# Ampli_FI2.net
KiCad netlist of a schematic drawn in Altium Designer
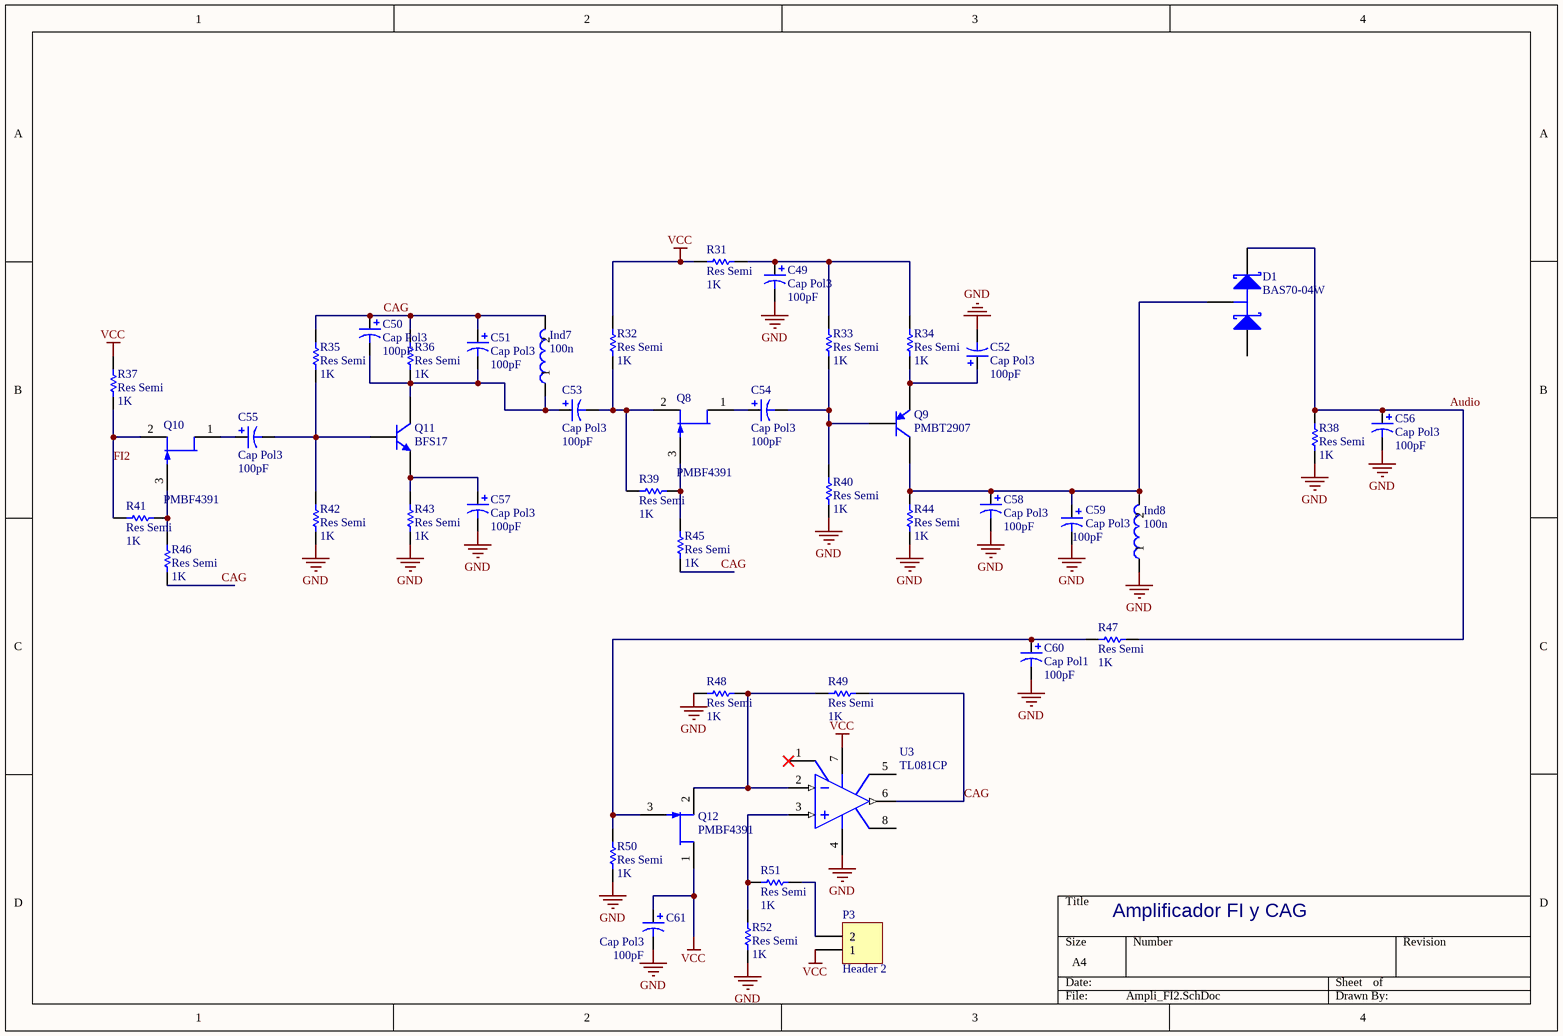
[diagram p0: Ampli_FI2.SchDoc]

(export (version "E")
  (design (tool "Eeschema 10.0.6"))
  (components
    (comp (ref "C49")
      (value "Cap Pol3")
      (footprint "C0805")
      (description "Polarized Capacitor (Surface Mount)")
      (fields (field (name "ALTIUM_VALUE") "100pF") (field (name "PUBLISHER") "Altium Limited"))
      (libsource (lib "Miscellaneous Devices") (part "Cap Pol3"))
    )
    (comp (ref "C50")
      (value "Cap Pol3")
      (footprint "C0805")
      (description "Polarized Capacitor (Surface Mount)")
      (fields (field (name "ALTIUM_VALUE") "100pF") (field (name "PUBLISHER") "Altium Limited"))
      (libsource (lib "Miscellaneous Devices") (part "Cap Pol3"))
    )
    (comp (ref "C51")
      (value "Cap Pol3")
      (footprint "C0805")
      (description "Polarized Capacitor (Surface Mount)")
      (fields (field (name "ALTIUM_VALUE") "100pF") (field (name "PUBLISHER") "Altium Limited"))
      (libsource (lib "Miscellaneous Devices") (part "Cap Pol3"))
    )
    (comp (ref "C52")
      (value "Cap Pol3")
      (footprint "C0805")
      (description "Polarized Capacitor (Surface Mount)")
      (fields (field (name "ALTIUM_VALUE") "100pF") (field (name "PUBLISHER") "Altium Limited"))
      (libsource (lib "Miscellaneous Devices") (part "Cap Pol3"))
    )
    (comp (ref "C53")
      (value "Cap Pol3")
      (footprint "C0805")
      (description "Polarized Capacitor (Surface Mount)")
      (fields (field (name "ALTIUM_VALUE") "100pF") (field (name "PUBLISHER") "Altium Limited"))
      (libsource (lib "Miscellaneous Devices") (part "Cap Pol3"))
    )
    (comp (ref "C54")
      (value "Cap Pol3")
      (footprint "C0805")
      (description "Polarized Capacitor (Surface Mount)")
      (fields (field (name "ALTIUM_VALUE") "100pF") (field (name "PUBLISHER") "Altium Limited"))
      (libsource (lib "Miscellaneous Devices") (part "Cap Pol3"))
    )
    (comp (ref "C55")
      (value "Cap Pol3")
      (footprint "C0805")
      (description "Polarized Capacitor (Surface Mount)")
      (fields (field (name "ALTIUM_VALUE") "100pF") (field (name "PUBLISHER") "Altium Limited"))
      (libsource (lib "Miscellaneous Devices") (part "Cap Pol3"))
    )
    (comp (ref "C56")
      (value "Cap Pol3")
      (footprint "C0805")
      (description "Polarized Capacitor (Surface Mount)")
      (fields (field (name "ALTIUM_VALUE") "100pF") (field (name "PUBLISHER") "Altium Limited"))
      (libsource (lib "Miscellaneous Devices") (part "Cap Pol3"))
    )
    (comp (ref "C57")
      (value "Cap Pol3")
      (footprint "C0805")
      (description "Polarized Capacitor (Surface Mount)")
      (fields (field (name "ALTIUM_VALUE") "100pF") (field (name "PUBLISHER") "Altium Limited"))
      (libsource (lib "Miscellaneous Devices") (part "Cap Pol3"))
    )
    (comp (ref "C58")
      (value "Cap Pol3")
      (footprint "C0805")
      (description "Polarized Capacitor (Surface Mount)")
      (fields (field (name "ALTIUM_VALUE") "100pF") (field (name "PUBLISHER") "Altium Limited"))
      (libsource (lib "Miscellaneous Devices") (part "Cap Pol3"))
    )
    (comp (ref "C59")
      (value "Cap Pol3")
      (footprint "C0805")
      (description "Polarized Capacitor (Surface Mount)")
      (fields (field (name "ALTIUM_VALUE") "100pF") (field (name "PUBLISHER") "Altium Limited"))
      (libsource (lib "Miscellaneous Devices") (part "Cap Pol3"))
    )
    (comp (ref "C60")
      (value "Cap Pol1")
      (footprint "B")
      (description "Polarized Capacitor (Radial)")
      (fields (field (name "ALTIUM_VALUE") "100pF") (field (name "PUBLISHER") "Altium Limited"))
      (libsource (lib "Miscellaneous Devices") (part "Cap Pol1"))
    )
    (comp (ref "C61")
      (value "Cap Pol3")
      (footprint "C0805")
      (description "Polarized Capacitor (Surface Mount)")
      (fields (field (name "ALTIUM_VALUE") "100pF") (field (name "PUBLISHER") "Altium Limited"))
      (libsource (lib "Miscellaneous Devices") (part "Cap Pol3"))
    )
    (comp (ref "D1")
      (value "BAS70-04W")
      (footprint "SOT323_N")
      (description "Schottky Barrier Double Diode")
      (fields (field (name "PUBLISHER") "Altium Limited"))
      (libsource (lib "Philips Discrete Diode - Schottky") (part "BAS70-04W"))
    )
    (comp (ref "Ind7")
      (value "Ind2")
      (footprint "AXIAL-0.3")
      (fields (field (name "VALOR") "100n"))
      (libsource (lib "epf") (part "Ind2"))
    )
    (comp (ref "Ind8")
      (value "Ind2")
      (footprint "AXIAL-0.3")
      (fields (field (name "VALOR") "100n"))
      (libsource (lib "epf") (part "Ind2"))
    )
    (comp (ref "P3")
      (value "Header 2")
      (footprint "HDR1X2")
      (description "Header, 2-Pin")
      (fields (field (name "PUBLISHER") "Altium Limited"))
      (libsource (lib "Miscellaneous Connectors") (part "Header 2"))
    )
    (comp (ref "Q8")
      (value "PMBF4391")
      (footprint "SOT-23")
      (description "N-channel Silicon Junction Field-effect Transistor")
      (fields (field (name "PUBLISHER") "Altium Limited"))
      (libsource (lib "Philips Discrete JFET") (part "PMBF4391"))
    )
    (comp (ref "Q9")
      (value "PMBT2907")
      (footprint "SOT-23")
      (description "PNP Switching Transistor")
      (fields (field (name "PUBLISHER") "Altium Limited"))
      (libsource (lib "Philips Discrete BJT - Low Power") (part "PMBT2907"))
    )
    (comp (ref "Q10")
      (value "PMBF4391")
      (footprint "SOT-23")
      (description "N-channel Silicon Junction Field-effect Transistor")
      (fields (field (name "PUBLISHER") "Altium Limited"))
      (libsource (lib "Philips Discrete JFET") (part "PMBF4391"))
    )
    (comp (ref "Q11")
      (value "BFS17")
      (footprint "SOT-23")
      (description "NPN 1 GHz Wideband Transistor")
      (fields (field (name "PUBLISHER") "Altium Limited"))
      (libsource (lib "Philips Discrete BJT - RF Transistor") (part "BFS17"))
    )
    (comp (ref "Q12")
      (value "PMBF4391")
      (footprint "SOT-23")
      (description "N-channel Silicon Junction Field-effect Transistor")
      (fields (field (name "PUBLISHER") "Altium Limited"))
      (libsource (lib "Philips Discrete JFET") (part "PMBF4391"))
    )
    (comp (ref "R31")
      (value "Res Semi")
      (footprint "2012[0805]")
      (description "Semiconductor Resistor")
      (fields (field (name "ALTIUM_VALUE") "1K") (field (name "PUBLISHER") "Altium Limited"))
      (libsource (lib "Miscellaneous Devices") (part "Res Semi"))
    )
    (comp (ref "R32")
      (value "Res Semi")
      (footprint "2012[0805]")
      (description "Semiconductor Resistor")
      (fields (field (name "ALTIUM_VALUE") "1K") (field (name "PUBLISHER") "Altium Limited"))
      (libsource (lib "Miscellaneous Devices") (part "Res Semi"))
    )
    (comp (ref "R33")
      (value "Res Semi")
      (footprint "2012[0805]")
      (description "Semiconductor Resistor")
      (fields (field (name "ALTIUM_VALUE") "1K") (field (name "PUBLISHER") "Altium Limited"))
      (libsource (lib "Miscellaneous Devices") (part "Res Semi"))
    )
    (comp (ref "R34")
      (value "Res Semi")
      (footprint "2012[0805]")
      (description "Semiconductor Resistor")
      (fields (field (name "ALTIUM_VALUE") "1K") (field (name "PUBLISHER") "Altium Limited"))
      (libsource (lib "Miscellaneous Devices") (part "Res Semi"))
    )
    (comp (ref "R35")
      (value "Res Semi")
      (footprint "2012[0805]")
      (description "Semiconductor Resistor")
      (fields (field (name "ALTIUM_VALUE") "1K") (field (name "PUBLISHER") "Altium Limited"))
      (libsource (lib "Miscellaneous Devices") (part "Res Semi"))
    )
    (comp (ref "R36")
      (value "Res Semi")
      (footprint "2012[0805]")
      (description "Semiconductor Resistor")
      (fields (field (name "ALTIUM_VALUE") "1K") (field (name "PUBLISHER") "Altium Limited"))
      (libsource (lib "Miscellaneous Devices") (part "Res Semi"))
    )
    (comp (ref "R37")
      (value "Res Semi")
      (footprint "2012[0805]")
      (description "Semiconductor Resistor")
      (fields (field (name "ALTIUM_VALUE") "1K") (field (name "PUBLISHER") "Altium Limited"))
      (libsource (lib "Miscellaneous Devices") (part "Res Semi"))
    )
    (comp (ref "R38")
      (value "Res Semi")
      (footprint "2012[0805]")
      (description "Semiconductor Resistor")
      (fields (field (name "ALTIUM_VALUE") "1K") (field (name "PUBLISHER") "Altium Limited"))
      (libsource (lib "Miscellaneous Devices") (part "Res Semi"))
    )
    (comp (ref "R39")
      (value "Res Semi")
      (footprint "2012[0805]")
      (description "Semiconductor Resistor")
      (fields (field (name "ALTIUM_VALUE") "1K") (field (name "PUBLISHER") "Altium Limited"))
      (libsource (lib "Miscellaneous Devices") (part "Res Semi"))
    )
    (comp (ref "R40")
      (value "Res Semi")
      (footprint "2012[0805]")
      (description "Semiconductor Resistor")
      (fields (field (name "ALTIUM_VALUE") "1K") (field (name "PUBLISHER") "Altium Limited"))
      (libsource (lib "Miscellaneous Devices") (part "Res Semi"))
    )
    (comp (ref "R41")
      (value "Res Semi")
      (footprint "2012[0805]")
      (description "Semiconductor Resistor")
      (fields (field (name "ALTIUM_VALUE") "1K") (field (name "PUBLISHER") "Altium Limited"))
      (libsource (lib "Miscellaneous Devices") (part "Res Semi"))
    )
    (comp (ref "R42")
      (value "Res Semi")
      (footprint "2012[0805]")
      (description "Semiconductor Resistor")
      (fields (field (name "ALTIUM_VALUE") "1K") (field (name "PUBLISHER") "Altium Limited"))
      (libsource (lib "Miscellaneous Devices") (part "Res Semi"))
    )
    (comp (ref "R43")
      (value "Res Semi")
      (footprint "2012[0805]")
      (description "Semiconductor Resistor")
      (fields (field (name "ALTIUM_VALUE") "1K") (field (name "PUBLISHER") "Altium Limited"))
      (libsource (lib "Miscellaneous Devices") (part "Res Semi"))
    )
    (comp (ref "R44")
      (value "Res Semi")
      (footprint "2012[0805]")
      (description "Semiconductor Resistor")
      (fields (field (name "ALTIUM_VALUE") "1K") (field (name "PUBLISHER") "Altium Limited"))
      (libsource (lib "Miscellaneous Devices") (part "Res Semi"))
    )
    (comp (ref "R45")
      (value "Res Semi")
      (footprint "2012[0805]")
      (description "Semiconductor Resistor")
      (fields (field (name "ALTIUM_VALUE") "1K") (field (name "PUBLISHER") "Altium Limited"))
      (libsource (lib "Miscellaneous Devices") (part "Res Semi"))
    )
    (comp (ref "R46")
      (value "Res Semi")
      (footprint "2012[0805]")
      (description "Semiconductor Resistor")
      (fields (field (name "ALTIUM_VALUE") "1K") (field (name "PUBLISHER") "Altium Limited"))
      (libsource (lib "Miscellaneous Devices") (part "Res Semi"))
    )
    (comp (ref "R47")
      (value "Res Semi")
      (footprint "2012[0805]")
      (description "Semiconductor Resistor")
      (fields (field (name "ALTIUM_VALUE") "1K") (field (name "PUBLISHER") "Altium Limited"))
      (libsource (lib "Miscellaneous Devices") (part "Res Semi"))
    )
    (comp (ref "R48")
      (value "Res Semi")
      (footprint "2012[0805]")
      (description "Semiconductor Resistor")
      (fields (field (name "ALTIUM_VALUE") "1K") (field (name "PUBLISHER") "Altium Limited"))
      (libsource (lib "Miscellaneous Devices") (part "Res Semi"))
    )
    (comp (ref "R49")
      (value "Res Semi")
      (footprint "2012[0805]")
      (description "Semiconductor Resistor")
      (fields (field (name "ALTIUM_VALUE") "1K") (field (name "PUBLISHER") "Altium Limited"))
      (libsource (lib "Miscellaneous Devices") (part "Res Semi"))
    )
    (comp (ref "R50")
      (value "Res Semi")
      (footprint "2012[0805]")
      (description "Semiconductor Resistor")
      (fields (field (name "ALTIUM_VALUE") "1K") (field (name "PUBLISHER") "Altium Limited"))
      (libsource (lib "Miscellaneous Devices") (part "Res Semi"))
    )
    (comp (ref "R51")
      (value "Res Semi")
      (footprint "2012[0805]")
      (description "Semiconductor Resistor")
      (fields (field (name "ALTIUM_VALUE") "1K") (field (name "PUBLISHER") "Altium Limited"))
      (libsource (lib "Miscellaneous Devices") (part "Res Semi"))
    )
    (comp (ref "R52")
      (value "Res Semi")
      (footprint "2012[0805]")
      (description "Semiconductor Resistor")
      (fields (field (name "ALTIUM_VALUE") "1K") (field (name "PUBLISHER") "Altium Limited"))
      (libsource (lib "Miscellaneous Devices") (part "Res Semi"))
    )
    (comp (ref "U3")
      (value "TL081CP")
      (footprint "DIP8")
      (description "JFET-Input Operational Amplifier")
      (fields (field (name "PUBLISHER") "Altium Limited"))
      (libsource (lib "Motorola Amplifier Operational Amplifier") (part "TL081CP"))
    )
  )
  (nets
    (net (code "1") (name "/Audio") (class "Default")
      (node (ref "C56") (pin "1") (pinfunction "1_1") (pintype "passive"))
      (node (ref "D1") (pin "2") (pinfunction "K_2") (pintype "passive"))
      (node (ref "R38") (pin "2") (pinfunction "2_2") (pintype "passive"))
      (node (ref "R47") (pin "1") (pinfunction "1_1") (pintype "passive"))
    )
    (net (code "2") (name "/CAG") (class "Default")
      (node (ref "C50") (pin "1") (pinfunction "1_1") (pintype "passive"))
      (node (ref "C51") (pin "1") (pinfunction "1_1") (pintype "passive"))
      (node (ref "Ind7") (pin "2") (pinfunction "2_2") (pintype "passive"))
      (node (ref "R35") (pin "2") (pinfunction "2_2") (pintype "passive"))
      (node (ref "R36") (pin "2") (pinfunction "2_2") (pintype "passive"))
      (node (ref "R45") (pin "2") (pinfunction "2_2") (pintype "passive"))
      (node (ref "R46") (pin "2") (pinfunction "2_2") (pintype "passive"))
      (node (ref "R49") (pin "2") (pinfunction "2_2") (pintype "passive"))
      (node (ref "U3") (pin "6") (pinfunction "OUT_6") (pintype "output"))
    )
    (net (code "3") (name "/FI2") (class "Default")
      (node (ref "Q10") (pin "2") (pinfunction "S_2") (pintype "passive"))
      (node (ref "R37") (pin "2") (pinfunction "2_2") (pintype "passive"))
      (node (ref "R41") (pin "1") (pinfunction "1_1") (pintype "passive"))
    )
    (net (code "4") (name "GND") (class "Default")
      (node (ref "C49") (pin "2") (pinfunction "2_2") (pintype "passive"))
      (node (ref "C52") (pin "2") (pinfunction "2_2") (pintype "passive"))
      (node (ref "C56") (pin "2") (pinfunction "2_2") (pintype "passive"))
      (node (ref "C57") (pin "2") (pinfunction "2_2") (pintype "passive"))
      (node (ref "C58") (pin "2") (pinfunction "2_2") (pintype "passive"))
      (node (ref "C59") (pin "2") (pinfunction "2_2") (pintype "passive"))
      (node (ref "C60") (pin "2") (pinfunction "2_2") (pintype "passive"))
      (node (ref "C61") (pin "2") (pinfunction "2_2") (pintype "passive"))
      (node (ref "Ind8") (pin "1") (pinfunction "1_1") (pintype "passive"))
      (node (ref "R38") (pin "1") (pinfunction "1_1") (pintype "passive"))
      (node (ref "R40") (pin "2") (pinfunction "2_2") (pintype "passive"))
      (node (ref "R42") (pin "1") (pinfunction "1_1") (pintype "passive"))
      (node (ref "R43") (pin "1") (pinfunction "1_1") (pintype "passive"))
      (node (ref "R44") (pin "2") (pinfunction "2_2") (pintype "passive"))
      (node (ref "R48") (pin "1") (pinfunction "1_1") (pintype "passive"))
      (node (ref "R50") (pin "2") (pinfunction "2_2") (pintype "passive"))
      (node (ref "R52") (pin "2") (pinfunction "2_2") (pintype "passive"))
      (node (ref "U3") (pin "4") (pinfunction "V-_4") (pintype "power_in"))
    )
    (net (code "5") (name "Net-(C49-Pad1)") (class "Default")
      (node (ref "C49") (pin "1") (pinfunction "1_1") (pintype "passive"))
      (node (ref "R31") (pin "1") (pinfunction "1_1") (pintype "passive"))
      (node (ref "R33") (pin "1") (pinfunction "1_1") (pintype "passive"))
      (node (ref "R34") (pin "1") (pinfunction "1_1") (pintype "passive"))
    )
    (net (code "6") (name "Net-(D1-C)") (class "Default")
      (node (ref "C58") (pin "1") (pinfunction "1_1") (pintype "passive"))
      (node (ref "C59") (pin "1") (pinfunction "1_1") (pintype "passive"))
      (node (ref "D1") (pin "3") (pinfunction "C_3") (pintype "passive"))
      (node (ref "Ind8") (pin "2") (pinfunction "2_2") (pintype "passive"))
      (node (ref "Q9") (pin "3") (pinfunction "C_3") (pintype "passive"))
      (node (ref "R44") (pin "1") (pinfunction "1_1") (pintype "passive"))
    )
    (net (code "7") (name "Net-(P3-Pad2)") (class "Default")
      (node (ref "P3") (pin "2") (pinfunction "2_2") (pintype "passive"))
      (node (ref "R51") (pin "1") (pinfunction "1_1") (pintype "passive"))
    )
    (net (code "8") (name "Net-(Q8-D)") (class "Default")
      (node (ref "C54") (pin "1") (pinfunction "1_1") (pintype "passive"))
      (node (ref "Q8") (pin "1") (pinfunction "D_1") (pintype "passive"))
    )
    (net (code "9") (name "Net-(Q8-G)") (class "Default")
      (node (ref "Q8") (pin "3") (pinfunction "G_3") (pintype "passive"))
      (node (ref "R39") (pin "2") (pinfunction "2_2") (pintype "passive"))
      (node (ref "R45") (pin "1") (pinfunction "1_1") (pintype "passive"))
    )
    (net (code "10") (name "Net-(Q8-S)") (class "Default")
      (node (ref "C53") (pin "2") (pinfunction "2_2") (pintype "passive"))
      (node (ref "Q8") (pin "2") (pinfunction "S_2") (pintype "passive"))
      (node (ref "R32") (pin "1") (pinfunction "1_1") (pintype "passive"))
      (node (ref "R39") (pin "1") (pinfunction "1_1") (pintype "passive"))
    )
    (net (code "11") (name "Net-(Q9-B)") (class "Default")
      (node (ref "C54") (pin "2") (pinfunction "2_2") (pintype "passive"))
      (node (ref "Q9") (pin "1") (pinfunction "B_1") (pintype "passive"))
      (node (ref "R33") (pin "2") (pinfunction "2_2") (pintype "passive"))
      (node (ref "R40") (pin "1") (pinfunction "1_1") (pintype "passive"))
    )
    (net (code "12") (name "Net-(Q9-E)") (class "Default")
      (node (ref "C52") (pin "1") (pinfunction "1_1") (pintype "passive"))
      (node (ref "Q9") (pin "2") (pinfunction "E_2") (pintype "passive"))
      (node (ref "R34") (pin "2") (pinfunction "2_2") (pintype "passive"))
    )
    (net (code "13") (name "Net-(Q10-D)") (class "Default")
      (node (ref "C55") (pin "1") (pinfunction "1_1") (pintype "passive"))
      (node (ref "Q10") (pin "1") (pinfunction "D_1") (pintype "passive"))
    )
    (net (code "14") (name "Net-(Q10-G)") (class "Default")
      (node (ref "Q10") (pin "3") (pinfunction "G_3") (pintype "passive"))
      (node (ref "R41") (pin "2") (pinfunction "2_2") (pintype "passive"))
      (node (ref "R46") (pin "1") (pinfunction "1_1") (pintype "passive"))
    )
    (net (code "15") (name "Net-(Q11-B)") (class "Default")
      (node (ref "C55") (pin "2") (pinfunction "2_2") (pintype "passive"))
      (node (ref "Q11") (pin "1") (pinfunction "B_1") (pintype "passive"))
      (node (ref "R35") (pin "1") (pinfunction "1_1") (pintype "passive"))
      (node (ref "R42") (pin "2") (pinfunction "2_2") (pintype "passive"))
    )
    (net (code "16") (name "Net-(Q11-C)") (class "Default")
      (node (ref "C50") (pin "2") (pinfunction "2_2") (pintype "passive"))
      (node (ref "C51") (pin "2") (pinfunction "2_2") (pintype "passive"))
      (node (ref "C53") (pin "1") (pinfunction "1_1") (pintype "passive"))
      (node (ref "Ind7") (pin "1") (pinfunction "1_1") (pintype "passive"))
      (node (ref "Q11") (pin "3") (pinfunction "C_3") (pintype "passive"))
      (node (ref "R36") (pin "1") (pinfunction "1_1") (pintype "passive"))
    )
    (net (code "17") (name "Net-(Q11-E)") (class "Default")
      (node (ref "C57") (pin "1") (pinfunction "1_1") (pintype "passive"))
      (node (ref "Q11") (pin "2") (pinfunction "E_2") (pintype "passive"))
      (node (ref "R43") (pin "2") (pinfunction "2_2") (pintype "passive"))
    )
    (net (code "18") (name "Net-(Q12-G)") (class "Default")
      (node (ref "C60") (pin "1") (pinfunction "1_1") (pintype "passive"))
      (node (ref "Q12") (pin "3") (pinfunction "G_3") (pintype "passive"))
      (node (ref "R47") (pin "2") (pinfunction "2_2") (pintype "passive"))
      (node (ref "R50") (pin "1") (pinfunction "1_1") (pintype "passive"))
    )
    (net (code "19") (name "Net-(Q12-S)") (class "Default")
      (node (ref "Q12") (pin "2") (pinfunction "S_2") (pintype "passive"))
      (node (ref "R48") (pin "2") (pinfunction "2_2") (pintype "passive"))
      (node (ref "R49") (pin "1") (pinfunction "1_1") (pintype "passive"))
      (node (ref "U3") (pin "2") (pinfunction "IN-_2") (pintype "input"))
    )
    (net (code "20") (name "Net-(U3-IN+)") (class "Default")
      (node (ref "R51") (pin "2") (pinfunction "2_2") (pintype "passive"))
      (node (ref "R52") (pin "1") (pinfunction "1_1") (pintype "passive"))
      (node (ref "U3") (pin "3") (pinfunction "IN+_3") (pintype "input"))
    )
    (net (code "21") (name "VCC") (class "Default")
      (node (ref "C61") (pin "1") (pinfunction "1_1") (pintype "passive"))
      (node (ref "P3") (pin "1") (pinfunction "1_1") (pintype "passive"))
      (node (ref "Q12") (pin "1") (pinfunction "D_1") (pintype "passive"))
      (node (ref "R31") (pin "2") (pinfunction "2_2") (pintype "passive"))
      (node (ref "R32") (pin "2") (pinfunction "2_2") (pintype "passive"))
      (node (ref "R37") (pin "1") (pinfunction "1_1") (pintype "passive"))
      (node (ref "U3") (pin "7") (pinfunction "V+_7") (pintype "power_in"))
    )
    (net (code "22") (name "unconnected-(D1-A-Pad1)") (class "Default")
      (node (ref "D1") (pin "1") (pinfunction "A_1") (pintype "passive"))
    )
    (net (code "23") (name "unconnected-(U3-NC-Pad8)") (class "Default")
      (node (ref "U3") (pin "8") (pinfunction "NC_8") (pintype "passive"))
    )
    (net (code "24") (name "unconnected-(U3-OS_NULL-Pad1)") (class "Default")
      (node (ref "U3") (pin "1") (pinfunction "OS_NULL_1") (pintype "passive+no_connect"))
    )
    (net (code "25") (name "unconnected-(U3-OS_NULL-Pad5)") (class "Default")
      (node (ref "U3") (pin "5") (pinfunction "OS_NULL_5") (pintype "passive"))
    )
  )
)
